# SCh_H_bridge.net
KiCad netlist of a schematic drawn in EAGLE
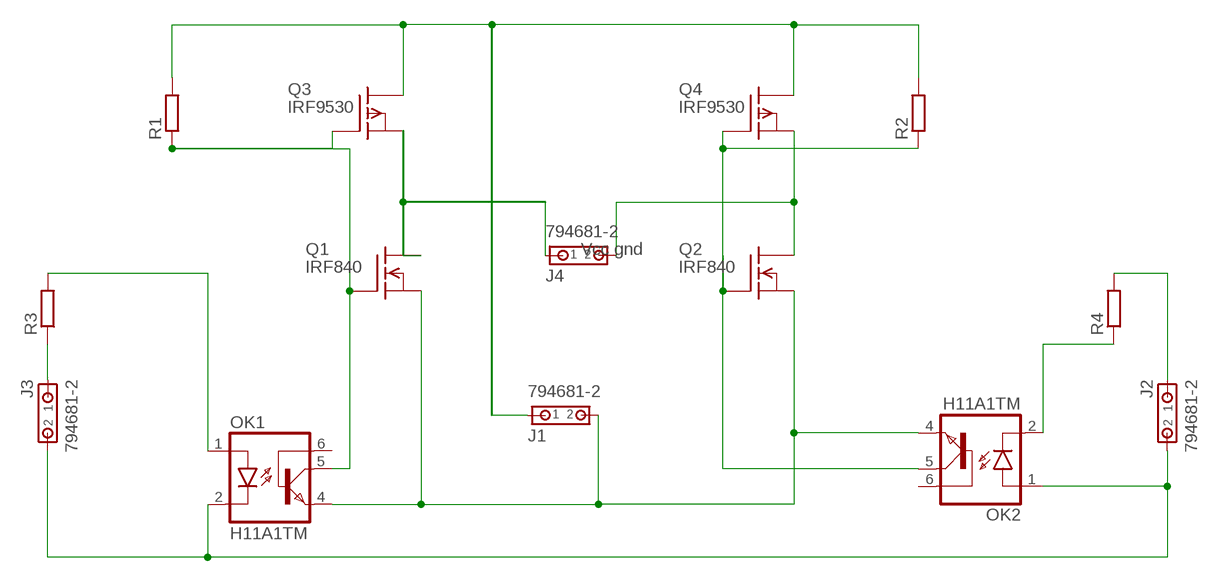
[diagram p0: schematic, sheet 1]

(export (version "E")
  (design (tool "Eeschema 10.0.6"))
  (components
    (comp (ref "J1")
      (value "794681-2")
      (footprint "eagle-import:794681-2")
      (libsource (lib "eagle-import") (part "794681-2"))
    )
    (comp (ref "J2")
      (value "794681-2")
      (footprint "eagle-import:794681-2")
      (libsource (lib "eagle-import") (part "794681-2"))
    )
    (comp (ref "J3")
      (value "794681-2")
      (footprint "eagle-import:794681-2")
      (libsource (lib "eagle-import") (part "794681-2"))
    )
    (comp (ref "J4")
      (value "794681-2")
      (footprint "eagle-import:794681-2")
      (fields (field (name "POPULARITY") "0") (field (name "POPULARITY_1") "Vcc gnd"))
      (libsource (lib "eagle-import") (part "794681-2"))
    )
    (comp (ref "OK1")
      (value "H11A1TM")
      (footprint "eagle-import:DIL6-04")
      (fields (field (name "MF") "FAIRCHILD SEMICONDUCTOR") (field (name "MPN") "H11A1TV-M"))
      (libsource (lib "eagle-import") (part "H11A?MT1"))
    )
    (comp (ref "OK2")
      (value "H11A1TM")
      (footprint "eagle-import:DIL6-04")
      (fields (field (name "MF") "FAIRCHILD SEMICONDUCTOR") (field (name "MPN") "H11A1TV-M"))
      (libsource (lib "eagle-import") (part "H11A?MT1"))
    )
    (comp (ref "Q1")
      (value "IRF840")
      (footprint "eagle-import:TO220")
      (libsource (lib "eagle-import") (part "IRF840"))
    )
    (comp (ref "Q2")
      (value "IRF840")
      (footprint "eagle-import:TO220")
      (libsource (lib "eagle-import") (part "IRF840"))
    )
    (comp (ref "Q3")
      (value "IRF9530")
      (footprint "eagle-import:TO220")
      (libsource (lib "eagle-import") (part "IRF9530"))
    )
    (comp (ref "Q4")
      (value "IRF9530")
      (footprint "eagle-import:TO220")
      (libsource (lib "eagle-import") (part "IRF9530"))
    )
    (comp (ref "R1")
      (value "R-EU_0309/12")
      (footprint "eagle-import:0309_12")
      (libsource (lib "eagle-import") (part "R-EU_0309/12"))
    )
    (comp (ref "R2")
      (value "R-EU_0309/12")
      (footprint "eagle-import:0309_12")
      (libsource (lib "eagle-import") (part "R-EU_0309/12"))
    )
    (comp (ref "R3")
      (value "R-EU_0309/12")
      (footprint "eagle-import:0309_12")
      (libsource (lib "eagle-import") (part "R-EU_0309/12"))
    )
    (comp (ref "R4")
      (value "R-EU_0309/12")
      (footprint "eagle-import:0309_12")
      (libsource (lib "eagle-import") (part "R-EU_0309/12"))
    )
  )
  (nets
    (net (code "1") (name "Net-(J2-Pad1)") (class "Default")
      (node (ref "J2") (pin "1") (pinfunction "1_1") (pintype "passive"))
      (node (ref "R4") (pin "2") (pinfunction "2_2") (pintype "passive"))
    )
    (net (code "2") (name "Net-(J3-Pad1)") (class "Default")
      (node (ref "J3") (pin "1") (pinfunction "1_1") (pintype "passive"))
      (node (ref "R3") (pin "1") (pinfunction "1_1") (pintype "passive"))
    )
    (net (code "3") (name "Net-(OK1-A)") (class "Default")
      (node (ref "OK1") (pin "1") (pinfunction "A_1") (pintype "passive"))
      (node (ref "R3") (pin "2") (pinfunction "2_2") (pintype "passive"))
    )
    (net (code "4") (name "Net-(OK1-C)") (class "Default")
      (node (ref "J2") (pin "2") (pinfunction "2_2") (pintype "passive"))
      (node (ref "J3") (pin "2") (pinfunction "2_2") (pintype "passive"))
      (node (ref "OK1") (pin "2") (pinfunction "C_2") (pintype "passive"))
      (node (ref "OK2") (pin "1") (pinfunction "A_1") (pintype "passive"))
    )
    (net (code "5") (name "Net-(OK1-COL)") (class "Default")
      (node (ref "OK1") (pin "5") (pinfunction "COL_5") (pintype "passive"))
      (node (ref "Q1") (pin "1") (pinfunction "G_1") (pintype "passive"))
      (node (ref "Q3") (pin "1") (pinfunction "G_1") (pintype "passive"))
      (node (ref "R1") (pin "1") (pinfunction "1_1") (pintype "passive"))
    )
    (net (code "6") (name "Net-(OK1-EMI)") (class "Default")
      (node (ref "J1") (pin "2") (pinfunction "2_2") (pintype "passive"))
      (node (ref "OK1") (pin "4") (pinfunction "EMI_4") (pintype "passive"))
      (node (ref "OK2") (pin "4") (pinfunction "EMI_4") (pintype "passive"))
      (node (ref "Q1") (pin "3") (pinfunction "S_3") (pintype "passive"))
      (node (ref "Q2") (pin "3") (pinfunction "S_3") (pintype "passive"))
    )
    (net (code "7") (name "Net-(OK2-C)") (class "Default")
      (node (ref "OK2") (pin "2") (pinfunction "C_2") (pintype "passive"))
      (node (ref "R4") (pin "1") (pinfunction "1_1") (pintype "passive"))
    )
    (net (code "8") (name "Net-(OK2-COL)") (class "Default")
      (node (ref "OK2") (pin "5") (pinfunction "COL_5") (pintype "passive"))
      (node (ref "Q2") (pin "1") (pinfunction "G_1") (pintype "passive"))
      (node (ref "Q4") (pin "1") (pinfunction "G_1") (pintype "passive"))
      (node (ref "R2") (pin "1") (pinfunction "1_1") (pintype "passive"))
    )
    (net (code "9") (name "Net-(Q1-D)") (class "Default")
      (node (ref "J4") (pin "1") (pinfunction "1_1") (pintype "passive"))
      (node (ref "Q1") (pin "2") (pinfunction "D_2") (pintype "passive"))
      (node (ref "Q3") (pin "3") (pinfunction "S_3") (pintype "passive"))
    )
    (net (code "10") (name "Net-(Q2-D)") (class "Default")
      (node (ref "J4") (pin "2") (pinfunction "2_2") (pintype "passive"))
      (node (ref "Q2") (pin "2") (pinfunction "D_2") (pintype "passive"))
      (node (ref "Q4") (pin "3") (pinfunction "S_3") (pintype "passive"))
    )
    (net (code "11") (name "Net-(Q3-D)") (class "Default")
      (node (ref "J1") (pin "1") (pinfunction "1_1") (pintype "passive"))
      (node (ref "Q3") (pin "2") (pinfunction "D_2") (pintype "passive"))
      (node (ref "Q4") (pin "2") (pinfunction "D_2") (pintype "passive"))
      (node (ref "R1") (pin "2") (pinfunction "2_2") (pintype "passive"))
      (node (ref "R2") (pin "2") (pinfunction "2_2") (pintype "passive"))
    )
    (net (code "12") (name "unconnected-(OK1-BAS-Pad6)") (class "Default")
      (node (ref "OK1") (pin "6") (pinfunction "BAS_6") (pintype "passive"))
    )
    (net (code "13") (name "unconnected-(OK2-BAS-Pad6)") (class "Default")
      (node (ref "OK2") (pin "6") (pinfunction "BAS_6") (pintype "passive"))
    )
  )
)
